# PCB_final.net
KiCad netlist of a schematic drawn in EAGLE
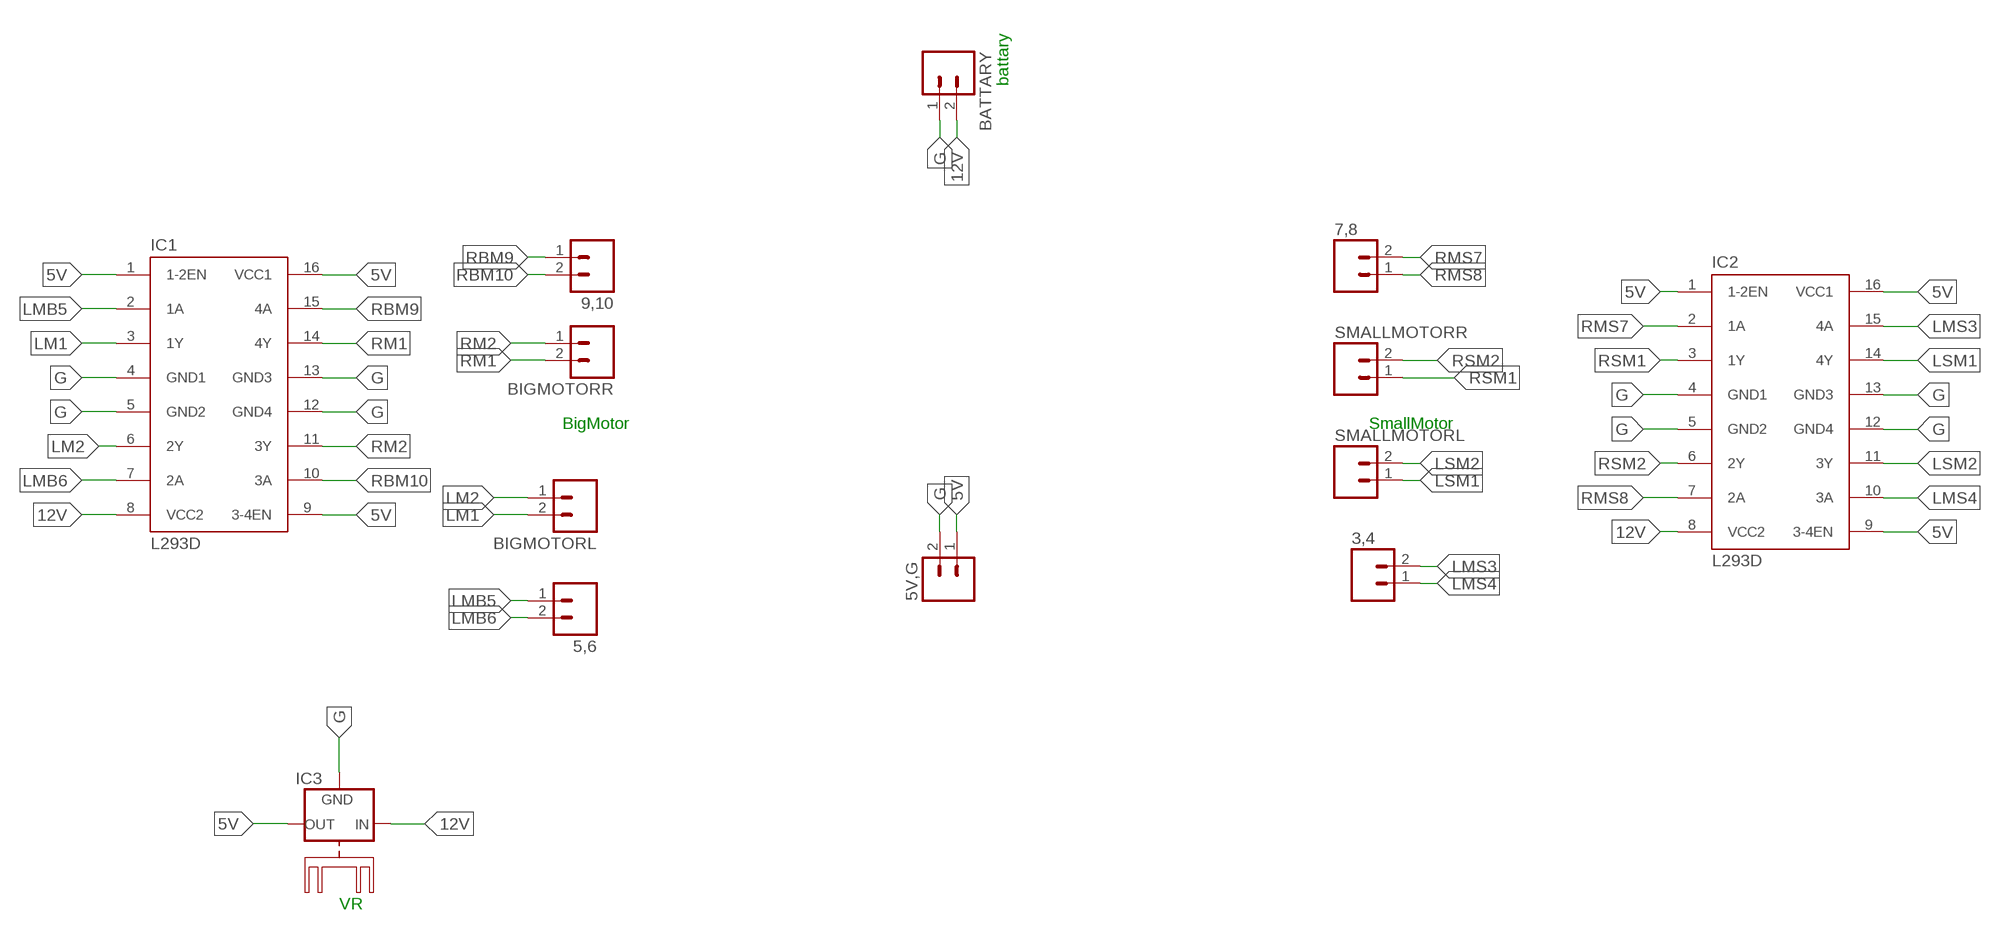
[diagram p0: schematic, sheet 1]

(export (version "E")
  (design (tool "Eeschema 10.0.6"))
  (components
    (comp (ref "3,4")
      (value "M02")
      (footprint "eagle-import:02P")
      (libsource (lib "eagle-import") (part "M02"))
    )
    (comp (ref "5,6")
      (value "M02")
      (footprint "eagle-import:02P")
      (libsource (lib "eagle-import") (part "M02"))
    )
    (comp (ref "5V,G")
      (value "M02")
      (footprint "eagle-import:02P")
      (libsource (lib "eagle-import") (part "M02"))
    )
    (comp (ref "7,8")
      (value "M02")
      (footprint "eagle-import:02P")
      (libsource (lib "eagle-import") (part "M02"))
    )
    (comp (ref "9,10")
      (value "M02")
      (footprint "eagle-import:02P")
      (libsource (lib "eagle-import") (part "M02"))
    )
    (comp (ref "BATTARY")
      (value "M02")
      (footprint "eagle-import:02P")
      (libsource (lib "eagle-import") (part "M02"))
    )
    (comp (ref "BIGMOTORL")
      (value "M02")
      (footprint "eagle-import:02P")
      (libsource (lib "eagle-import") (part "M02"))
    )
    (comp (ref "BIGMOTORR")
      (value "M02")
      (footprint "eagle-import:02P")
      (libsource (lib "eagle-import") (part "M02"))
    )
    (comp (ref "IC1")
      (value "L293D")
      (footprint "eagle-import:DIL16")
      (libsource (lib "eagle-import") (part "L293D"))
    )
    (comp (ref "IC2")
      (value "L293D")
      (footprint "eagle-import:DIL16")
      (libsource (lib "eagle-import") (part "L293D"))
    )
    (comp (ref "IC3")
      (value "78XXH")
      (footprint "eagle-import:78XXH")
      (libsource (lib "eagle-import") (part "78XXH"))
    )
    (comp (ref "SMALLMOTORL")
      (value "M02")
      (footprint "eagle-import:02P")
      (libsource (lib "eagle-import") (part "M02"))
    )
    (comp (ref "SMALLMOTORR")
      (value "M02")
      (footprint "eagle-import:02P")
      (libsource (lib "eagle-import") (part "M02"))
    )
  )
  (nets
    (net (code "1") (name "5V") (class "Default")
      (node (ref "5V,G") (pin "1") (pinfunction "1_1") (pintype "passive"))
      (node (ref "IC1") (pin "1") (pinfunction "1-2EN_1") (pintype "input"))
      (node (ref "IC1") (pin "16") (pinfunction "VCC1_16") (pintype "power_in"))
      (node (ref "IC1") (pin "9") (pinfunction "3-4EN_9") (pintype "input"))
      (node (ref "IC2") (pin "1") (pinfunction "1-2EN_1") (pintype "input"))
      (node (ref "IC2") (pin "16") (pinfunction "VCC1_16") (pintype "power_in"))
      (node (ref "IC2") (pin "9") (pinfunction "3-4EN_9") (pintype "input"))
      (node (ref "IC3") (pin "OUT") (pinfunction "OUT_OUT") (pintype "passive"))
    )
    (net (code "2") (name "12V") (class "Default")
      (node (ref "BATTARY") (pin "2") (pinfunction "2_2") (pintype "passive"))
      (node (ref "IC1") (pin "8") (pinfunction "VCC2_8") (pintype "power_in"))
      (node (ref "IC2") (pin "8") (pinfunction "VCC2_8") (pintype "power_in"))
      (node (ref "IC3") (pin "IN") (pinfunction "IN_IN") (pintype "input"))
    )
    (net (code "3") (name "G") (class "Default")
      (node (ref "5V,G") (pin "2") (pinfunction "2_2") (pintype "passive"))
      (node (ref "BATTARY") (pin "1") (pinfunction "1_1") (pintype "passive"))
      (node (ref "IC1") (pin "12") (pinfunction "GND4_12") (pintype "power_in"))
      (node (ref "IC1") (pin "13") (pinfunction "GND3_13") (pintype "power_in"))
      (node (ref "IC1") (pin "4") (pinfunction "GND1_4") (pintype "power_in"))
      (node (ref "IC1") (pin "5") (pinfunction "GND2_5") (pintype "power_in"))
      (node (ref "IC2") (pin "12") (pinfunction "GND4_12") (pintype "power_in"))
      (node (ref "IC2") (pin "13") (pinfunction "GND3_13") (pintype "power_in"))
      (node (ref "IC2") (pin "4") (pinfunction "GND1_4") (pintype "power_in"))
      (node (ref "IC2") (pin "5") (pinfunction "GND2_5") (pintype "power_in"))
      (node (ref "IC3") (pin "GND") (pinfunction "GND_GND") (pintype "input"))
    )
    (net (code "4") (name "LM1") (class "Default")
      (node (ref "BIGMOTORL") (pin "2") (pinfunction "2_2") (pintype "passive"))
      (node (ref "IC1") (pin "3") (pinfunction "1Y_3") (pintype "output"))
    )
    (net (code "5") (name "LM2") (class "Default")
      (node (ref "BIGMOTORL") (pin "1") (pinfunction "1_1") (pintype "passive"))
      (node (ref "IC1") (pin "6") (pinfunction "2Y_6") (pintype "output"))
    )
    (net (code "6") (name "LMB5") (class "Default")
      (node (ref "5,6") (pin "1") (pinfunction "1_1") (pintype "passive"))
      (node (ref "IC1") (pin "2") (pinfunction "1A_2") (pintype "input"))
    )
    (net (code "7") (name "LMB6") (class "Default")
      (node (ref "5,6") (pin "2") (pinfunction "2_2") (pintype "passive"))
      (node (ref "IC1") (pin "7") (pinfunction "2A_7") (pintype "input"))
    )
    (net (code "8") (name "LMS3") (class "Default")
      (node (ref "3,4") (pin "2") (pinfunction "2_2") (pintype "passive"))
      (node (ref "IC2") (pin "15") (pinfunction "4A_15") (pintype "input"))
    )
    (net (code "9") (name "LMS4") (class "Default")
      (node (ref "3,4") (pin "1") (pinfunction "1_1") (pintype "passive"))
      (node (ref "IC2") (pin "10") (pinfunction "3A_10") (pintype "input"))
    )
    (net (code "10") (name "LSM1") (class "Default")
      (node (ref "IC2") (pin "14") (pinfunction "4Y_14") (pintype "output"))
      (node (ref "SMALLMOTORL") (pin "1") (pinfunction "1_1") (pintype "passive"))
    )
    (net (code "11") (name "LSM2") (class "Default")
      (node (ref "IC2") (pin "11") (pinfunction "3Y_11") (pintype "output"))
      (node (ref "SMALLMOTORL") (pin "2") (pinfunction "2_2") (pintype "passive"))
    )
    (net (code "12") (name "RBM9") (class "Default")
      (node (ref "9,10") (pin "1") (pinfunction "1_1") (pintype "passive"))
      (node (ref "IC1") (pin "15") (pinfunction "4A_15") (pintype "input"))
    )
    (net (code "13") (name "RBM10") (class "Default")
      (node (ref "9,10") (pin "2") (pinfunction "2_2") (pintype "passive"))
      (node (ref "IC1") (pin "10") (pinfunction "3A_10") (pintype "input"))
    )
    (net (code "14") (name "RM1") (class "Default")
      (node (ref "BIGMOTORR") (pin "2") (pinfunction "2_2") (pintype "passive"))
      (node (ref "IC1") (pin "14") (pinfunction "4Y_14") (pintype "output"))
    )
    (net (code "15") (name "RM2") (class "Default")
      (node (ref "BIGMOTORR") (pin "1") (pinfunction "1_1") (pintype "passive"))
      (node (ref "IC1") (pin "11") (pinfunction "3Y_11") (pintype "output"))
    )
    (net (code "16") (name "RMS7") (class "Default")
      (node (ref "7,8") (pin "2") (pinfunction "2_2") (pintype "passive"))
      (node (ref "IC2") (pin "2") (pinfunction "1A_2") (pintype "input"))
    )
    (net (code "17") (name "RMS8") (class "Default")
      (node (ref "7,8") (pin "1") (pinfunction "1_1") (pintype "passive"))
      (node (ref "IC2") (pin "7") (pinfunction "2A_7") (pintype "input"))
    )
    (net (code "18") (name "RSM1") (class "Default")
      (node (ref "IC2") (pin "3") (pinfunction "1Y_3") (pintype "output"))
      (node (ref "SMALLMOTORR") (pin "1") (pinfunction "1_1") (pintype "passive"))
    )
    (net (code "19") (name "RSM2") (class "Default")
      (node (ref "IC2") (pin "6") (pinfunction "2Y_6") (pintype "output"))
      (node (ref "SMALLMOTORR") (pin "2") (pinfunction "2_2") (pintype "passive"))
    )
  )
)
